# counter_defender_mk_2.net
KiCad netlist of a schematic drawn in EAGLE
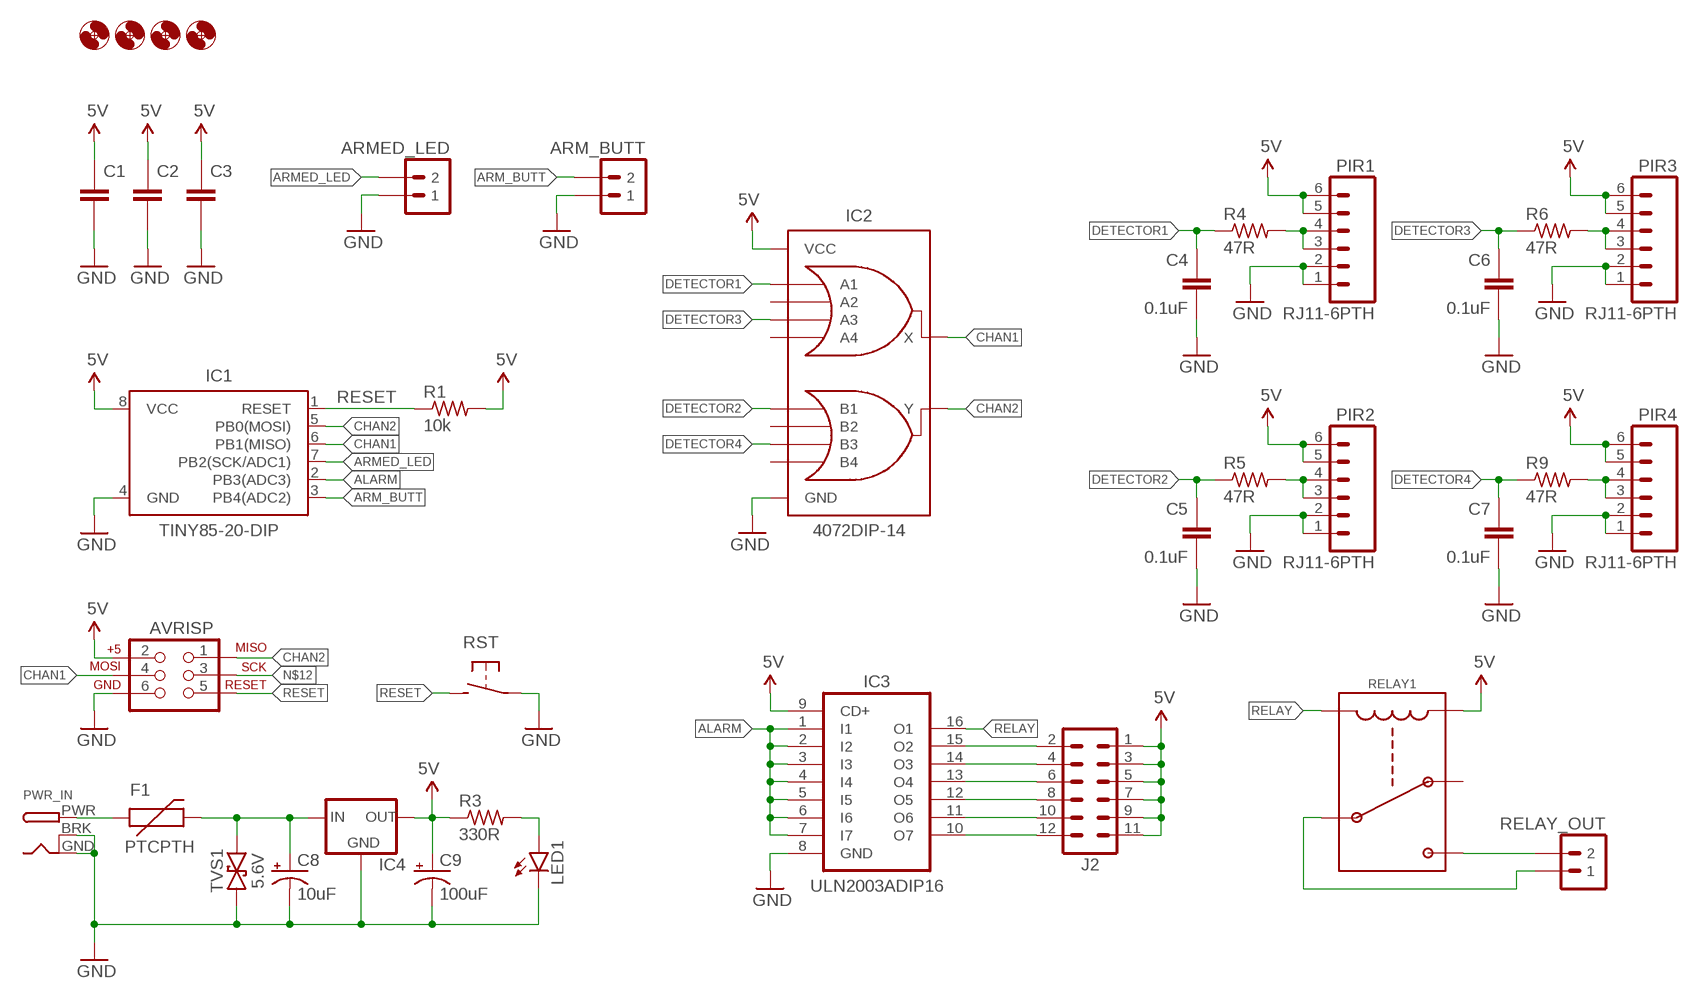
[diagram p0: schematic, sheet 1]

(export (version "E")
  (design (tool "Eeschema 10.0.6"))
  (components
    (comp (ref "ARMED_LED")
      (value "M02JST-PTH-VERT")
      (footprint "eagle-import:JST-2-PH-VERT-PTH")
      (libsource (lib "eagle-import") (part "M02JST-PTH-VERT"))
    )
    (comp (ref "ARM_BUTT")
      (value "M02JST-PTH-VERT")
      (footprint "eagle-import:JST-2-PH-VERT-PTH")
      (libsource (lib "eagle-import") (part "M02JST-PTH-VERT"))
    )
    (comp (ref "AVRISP")
      (value "AVR_SPI_PRG_6PTH")
      (footprint "eagle-import:2X3")
      (libsource (lib "eagle-import") (part "AVR_SPI_PRG_6PTH"))
    )
    (comp (ref "C1")
      (value "CAPACITOR-CERAMIC025-024X044")
      (footprint "eagle-import:C025-024X044")
      (libsource (lib "eagle-import") (part "CAPACITOR-CERAMIC025-024X044"))
    )
    (comp (ref "C2")
      (value "CAPACITOR-CERAMIC025-024X044")
      (footprint "eagle-import:C025-024X044")
      (libsource (lib "eagle-import") (part "CAPACITOR-CERAMIC025-024X044"))
    )
    (comp (ref "C3")
      (value "CAPACITOR-CERAMIC025-024X044")
      (footprint "eagle-import:C025-024X044")
      (libsource (lib "eagle-import") (part "CAPACITOR-CERAMIC025-024X044"))
    )
    (comp (ref "C4")
      (value "0.1uF")
      (footprint "eagle-import:C025-024X044")
      (libsource (lib "eagle-import") (part "CAPACITOR-CERAMIC025-024X044"))
    )
    (comp (ref "C5")
      (value "0.1uF")
      (footprint "eagle-import:C025-024X044")
      (libsource (lib "eagle-import") (part "CAPACITOR-CERAMIC025-024X044"))
    )
    (comp (ref "C6")
      (value "0.1uF")
      (footprint "eagle-import:C025-024X044")
      (libsource (lib "eagle-import") (part "CAPACITOR-CERAMIC025-024X044"))
    )
    (comp (ref "C7")
      (value "0.1uF")
      (footprint "eagle-import:C025-024X044")
      (libsource (lib "eagle-import") (part "CAPACITOR-CERAMIC025-024X044"))
    )
    (comp (ref "C8")
      (value "10uF")
      (footprint "eagle-import:E2-5")
      (libsource (lib "eagle-import") (part "CAPACITOR-POLARIZEDE2-5"))
    )
    (comp (ref "C9")
      (value "100uF")
      (footprint "eagle-import:E2,5-6")
      (libsource (lib "eagle-import") (part "CAPACITOR-POLARIZEDE2.5-6"))
    )
    (comp (ref "F1")
      (value "PTCPTH")
      (footprint "eagle-import:PTC")
      (libsource (lib "eagle-import") (part "PTCPTH"))
    )
    (comp (ref "H1")
      (value "HOLE#2")
      (footprint "eagle-import:HOLE-#2")
      (libsource (lib "eagle-import") (part "HOLE#2"))
    )
    (comp (ref "H2")
      (value "HOLE#2")
      (footprint "eagle-import:HOLE-#2")
      (libsource (lib "eagle-import") (part "HOLE#2"))
    )
    (comp (ref "H3")
      (value "HOLE#2")
      (footprint "eagle-import:HOLE-#2")
      (libsource (lib "eagle-import") (part "HOLE#2"))
    )
    (comp (ref "H4")
      (value "HOLE#2")
      (footprint "eagle-import:HOLE-#2")
      (libsource (lib "eagle-import") (part "HOLE#2"))
    )
    (comp (ref "IC1")
      (value "TINY85-20-DIP")
      (footprint "eagle-import:DIP08")
      (libsource (lib "eagle-import") (part "ATTINY45TINY85-20-DIP"))
    )
    (comp (ref "IC2")
      (value "4072DIP-14")
      (footprint "eagle-import:DIL14")
      (libsource (lib "eagle-import") (part "4072DIP-14"))
    )
    (comp (ref "IC3")
      (value "ULN2003ADIP16")
      (footprint "eagle-import:DIL16")
      (libsource (lib "eagle-import") (part "ULN2003ADIP16"))
    )
    (comp (ref "IC4")
      (value "L7805")
      (footprint "eagle-import:TO220V")
      (libsource (lib "eagle-import") (part "V_REG_78XXTO-220-IGO-VERT"))
    )
    (comp (ref "J2")
      (value "M06X2PTH")
      (footprint "eagle-import:2X6_PTH")
      (libsource (lib "eagle-import") (part "M06X2PTH"))
    )
    (comp (ref "LED1")
      (value "LED3MM")
      (footprint "eagle-import:LED3MM")
      (libsource (lib "eagle-import") (part "LED3MM"))
    )
    (comp (ref "PIR1")
      (value "RJ11-6PTH")
      (footprint "eagle-import:RJ11-6")
      (libsource (lib "eagle-import") (part "RJ11-6PTH"))
    )
    (comp (ref "PIR2")
      (value "RJ11-6PTH")
      (footprint "eagle-import:RJ11-6")
      (libsource (lib "eagle-import") (part "RJ11-6PTH"))
    )
    (comp (ref "PIR3")
      (value "RJ11-6PTH")
      (footprint "eagle-import:RJ11-6")
      (libsource (lib "eagle-import") (part "RJ11-6PTH"))
    )
    (comp (ref "PIR4")
      (value "RJ11-6PTH")
      (footprint "eagle-import:RJ11-6")
      (libsource (lib "eagle-import") (part "RJ11-6PTH"))
    )
    (comp (ref "PWR_IN")
      (value "DCBARRELPTH")
      (footprint "eagle-import:DCJACK_2MM_PTH")
      (libsource (lib "eagle-import") (part "DCBARRELPTH"))
    )
    (comp (ref "R1")
      (value "10k")
      (footprint "eagle-import:RESISTOR-AXIAL-PTH-6.35MM")
      (libsource (lib "eagle-import") (part "RESISTORPTH-AXIAL-6.35MM"))
    )
    (comp (ref "R3")
      (value "330R")
      (footprint "eagle-import:RESISTOR-AXIAL-PTH-6.35MM")
      (libsource (lib "eagle-import") (part "RESISTORPTH-AXIAL-6.35MM"))
    )
    (comp (ref "R4")
      (value "47R")
      (footprint "eagle-import:RESISTOR-AXIAL-PTH-6.35MM")
      (libsource (lib "eagle-import") (part "RESISTORPTH-AXIAL-6.35MM"))
    )
    (comp (ref "R5")
      (value "47R")
      (footprint "eagle-import:RESISTOR-AXIAL-PTH-6.35MM")
      (libsource (lib "eagle-import") (part "RESISTORPTH-AXIAL-6.35MM"))
    )
    (comp (ref "R6")
      (value "47R")
      (footprint "eagle-import:RESISTOR-AXIAL-PTH-6.35MM")
      (libsource (lib "eagle-import") (part "RESISTORPTH-AXIAL-6.35MM"))
    )
    (comp (ref "R9")
      (value "47R")
      (footprint "eagle-import:RESISTOR-AXIAL-PTH-6.35MM")
      (libsource (lib "eagle-import") (part "RESISTORPTH-AXIAL-6.35MM"))
    )
    (comp (ref "RELAY1")
      (value "RELAY-SPDTMC25120")
      (footprint "eagle-import:RELAY-SPDT-MC25120")
      (libsource (lib "eagle-import") (part "RELAY-SPDTMC25120"))
    )
    (comp (ref "RELAY_OUT")
      (value "M02SCREWTERM_2.54MM")
      (footprint "eagle-import:1X02_2.54_SCREWTERM")
      (libsource (lib "eagle-import") (part "M02SCREWTERM_2.54MM"))
    )
    (comp (ref "RST")
      (value "SPST-NO-TACT6MM-PTH")
      (footprint "eagle-import:DTS-6")
      (libsource (lib "eagle-import") (part "SPST-NO-TACT6MM-PTH"))
    )
    (comp (ref "TVS1")
      (value "5.6V")
      (footprint "eagle-import:DO-41-TVS")
      (libsource (lib "eagle-import") (part "TVSDO-41-TVS-BIDIRECTIONAL"))
    )
  )
  (nets
    (net (code "1") (name "5V") (class "Default")
      (node (ref "AVRISP") (pin "2") (pinfunction "2_2") (pintype "passive"))
      (node (ref "C1") (pin "1") (pinfunction "1_1") (pintype "passive"))
      (node (ref "C2") (pin "1") (pinfunction "1_1") (pintype "passive"))
      (node (ref "C3") (pin "1") (pinfunction "1_1") (pintype "passive"))
      (node (ref "C9") (pin "+") (pinfunction "+_+") (pintype "passive"))
      (node (ref "IC1") (pin "8") (pinfunction "VCC_8") (pintype "bidirectional"))
      (node (ref "IC2") (pin "14") (pinfunction "VCC_14") (pintype "bidirectional"))
      (node (ref "IC3") (pin "9") (pinfunction "CD+_9") (pintype "passive"))
      (node (ref "IC4") (pin "3") (pinfunction "OUT_3") (pintype "output"))
      (node (ref "J2") (pin "1") (pinfunction "1_1") (pintype "passive"))
      (node (ref "J2") (pin "11") (pinfunction "11_11") (pintype "passive"))
      (node (ref "J2") (pin "3") (pinfunction "3_3") (pintype "passive"))
      (node (ref "J2") (pin "5") (pinfunction "5_5") (pintype "passive"))
      (node (ref "J2") (pin "7") (pinfunction "7_7") (pintype "passive"))
      (node (ref "J2") (pin "9") (pinfunction "9_9") (pintype "passive"))
      (node (ref "PIR1") (pin "5") (pinfunction "5_5") (pintype "passive"))
      (node (ref "PIR1") (pin "6") (pinfunction "6_6") (pintype "passive"))
      (node (ref "PIR2") (pin "5") (pinfunction "5_5") (pintype "passive"))
      (node (ref "PIR2") (pin "6") (pinfunction "6_6") (pintype "passive"))
      (node (ref "PIR3") (pin "5") (pinfunction "5_5") (pintype "passive"))
      (node (ref "PIR3") (pin "6") (pinfunction "6_6") (pintype "passive"))
      (node (ref "PIR4") (pin "5") (pinfunction "5_5") (pintype "passive"))
      (node (ref "PIR4") (pin "6") (pinfunction "6_6") (pintype "passive"))
      (node (ref "R1") (pin "P$2") (pinfunction "2_P$2") (pintype "passive"))
      (node (ref "R3") (pin "P$1") (pinfunction "1_P$1") (pintype "passive"))
      (node (ref "RELAY1") (pin "CNTL2") (pinfunction "C$1_CNTL2") (pintype "bidirectional"))
    )
    (net (code "2") (name "ALARM") (class "Default")
      (node (ref "IC1") (pin "2") (pinfunction "PB3(ADC3)_2") (pintype "bidirectional"))
      (node (ref "IC3") (pin "1") (pinfunction "I1_1") (pintype "input"))
      (node (ref "IC3") (pin "2") (pinfunction "I2_2") (pintype "input"))
      (node (ref "IC3") (pin "3") (pinfunction "I3_3") (pintype "input"))
      (node (ref "IC3") (pin "4") (pinfunction "I4_4") (pintype "input"))
      (node (ref "IC3") (pin "5") (pinfunction "I5_5") (pintype "input"))
      (node (ref "IC3") (pin "6") (pinfunction "I6_6") (pintype "input"))
      (node (ref "IC3") (pin "7") (pinfunction "I7_7") (pintype "input"))
    )
    (net (code "3") (name "ARMED_LED") (class "Default")
      (node (ref "ARMED_LED") (pin "2") (pinfunction "2_2") (pintype "passive"))
      (node (ref "IC1") (pin "7") (pinfunction "PB2(SCK/ADC1)_7") (pintype "bidirectional"))
    )
    (net (code "4") (name "ARM_BUTT") (class "Default")
      (node (ref "ARM_BUTT") (pin "2") (pinfunction "2_2") (pintype "passive"))
      (node (ref "IC1") (pin "3") (pinfunction "PB4(ADC2)_3") (pintype "bidirectional"))
    )
    (net (code "5") (name "CHAN1") (class "Default")
      (node (ref "AVRISP") (pin "4") (pinfunction "4_4") (pintype "passive"))
      (node (ref "IC1") (pin "6") (pinfunction "PB1(MISO)_6") (pintype "bidirectional"))
      (node (ref "IC2") (pin "1") (pinfunction "X_1") (pintype "bidirectional"))
    )
    (net (code "6") (name "CHAN2") (class "Default")
      (node (ref "AVRISP") (pin "1") (pinfunction "1_1") (pintype "passive"))
      (node (ref "IC1") (pin "5") (pinfunction "PB0(MOSI)_5") (pintype "bidirectional"))
      (node (ref "IC2") (pin "13") (pinfunction "Y_13") (pintype "bidirectional"))
    )
    (net (code "7") (name "DETECTOR1") (class "Default")
      (node (ref "C4") (pin "1") (pinfunction "1_1") (pintype "passive"))
      (node (ref "IC2") (pin "2") (pinfunction "A1_2") (pintype "bidirectional"))
      (node (ref "R4") (pin "P$1") (pinfunction "1_P$1") (pintype "passive"))
    )
    (net (code "8") (name "DETECTOR2") (class "Default")
      (node (ref "C5") (pin "1") (pinfunction "1_1") (pintype "passive"))
      (node (ref "IC2") (pin "9") (pinfunction "B1_9") (pintype "bidirectional"))
      (node (ref "R5") (pin "P$1") (pinfunction "1_P$1") (pintype "passive"))
    )
    (net (code "9") (name "DETECTOR3") (class "Default")
      (node (ref "C6") (pin "1") (pinfunction "1_1") (pintype "passive"))
      (node (ref "IC2") (pin "4") (pinfunction "A3_4") (pintype "bidirectional"))
      (node (ref "R6") (pin "P$1") (pinfunction "1_P$1") (pintype "passive"))
    )
    (net (code "10") (name "DETECTOR4") (class "Default")
      (node (ref "C7") (pin "1") (pinfunction "1_1") (pintype "passive"))
      (node (ref "IC2") (pin "11") (pinfunction "B3_11") (pintype "bidirectional"))
      (node (ref "R9") (pin "P$1") (pinfunction "1_P$1") (pintype "passive"))
    )
    (net (code "11") (name "GND") (class "Default")
      (node (ref "ARMED_LED") (pin "1") (pinfunction "1_1") (pintype "passive"))
      (node (ref "ARM_BUTT") (pin "1") (pinfunction "1_1") (pintype "passive"))
      (node (ref "AVRISP") (pin "6") (pinfunction "6_6") (pintype "passive"))
      (node (ref "C1") (pin "2") (pinfunction "2_2") (pintype "passive"))
      (node (ref "C2") (pin "2") (pinfunction "2_2") (pintype "passive"))
      (node (ref "C3") (pin "2") (pinfunction "2_2") (pintype "passive"))
      (node (ref "C4") (pin "2") (pinfunction "2_2") (pintype "passive"))
      (node (ref "C5") (pin "2") (pinfunction "2_2") (pintype "passive"))
      (node (ref "C6") (pin "2") (pinfunction "2_2") (pintype "passive"))
      (node (ref "C7") (pin "2") (pinfunction "2_2") (pintype "passive"))
      (node (ref "C8") (pin "-") (pinfunction "-_-") (pintype "passive"))
      (node (ref "C9") (pin "-") (pinfunction "-_-") (pintype "passive"))
      (node (ref "IC1") (pin "4") (pinfunction "GND_4") (pintype "bidirectional"))
      (node (ref "IC2") (pin "7") (pinfunction "GND_7") (pintype "bidirectional"))
      (node (ref "IC3") (pin "8") (pinfunction "GND_8") (pintype "power_in"))
      (node (ref "IC4") (pin "2") (pinfunction "GND_2") (pintype "input"))
      (node (ref "LED1") (pin "K") (pinfunction "C_K") (pintype "passive"))
      (node (ref "PIR1") (pin "1") (pinfunction "1_1") (pintype "passive"))
      (node (ref "PIR1") (pin "2") (pinfunction "2_2") (pintype "passive"))
      (node (ref "PIR2") (pin "1") (pinfunction "1_1") (pintype "passive"))
      (node (ref "PIR2") (pin "2") (pinfunction "2_2") (pintype "passive"))
      (node (ref "PIR3") (pin "1") (pinfunction "1_1") (pintype "passive"))
      (node (ref "PIR3") (pin "2") (pinfunction "2_2") (pintype "passive"))
      (node (ref "PIR4") (pin "1") (pinfunction "1_1") (pintype "passive"))
      (node (ref "PIR4") (pin "2") (pinfunction "2_2") (pintype "passive"))
      (node (ref "PWR_IN") (pin "BRK") (pinfunction "BRK_BRK") (pintype "power_in"))
      (node (ref "PWR_IN") (pin "GND") (pinfunction "GND_GND") (pintype "power_in"))
      (node (ref "RST") (pin "1") (pinfunction "1_1") (pintype "passive"))
      (node (ref "RST") (pin "2") (pinfunction "1_2") (pintype "passive"))
      (node (ref "TVS1") (pin "P$1") (pinfunction "1_P$1") (pintype "passive"))
    )
    (net (code "12") (name "N$12") (class "Default")
      (node (ref "AVRISP") (pin "3") (pinfunction "3_3") (pintype "passive"))
    )
    (net (code "13") (name "Net-(F1-1)") (class "Default")
      (node (ref "F1") (pin "P$1") (pinfunction "1_P$1") (pintype "bidirectional"))
      (node (ref "PWR_IN") (pin "PWR") (pinfunction "PWR_PWR") (pintype "power_in"))
    )
    (net (code "14") (name "Net-(F1-2)") (class "Default")
      (node (ref "C8") (pin "+") (pinfunction "+_+") (pintype "passive"))
      (node (ref "F1") (pin "P$2") (pinfunction "2_P$2") (pintype "bidirectional"))
      (node (ref "IC4") (pin "1") (pinfunction "IN_1") (pintype "input"))
      (node (ref "TVS1") (pin "P$2") (pinfunction "2_P$2") (pintype "passive"))
    )
    (net (code "15") (name "Net-(IC3-O2)") (class "Default")
      (node (ref "IC3") (pin "15") (pinfunction "O2_15") (pintype "open_collector"))
      (node (ref "J2") (pin "2") (pinfunction "2_2") (pintype "passive"))
    )
    (net (code "16") (name "Net-(IC3-O3)") (class "Default")
      (node (ref "IC3") (pin "14") (pinfunction "O3_14") (pintype "open_collector"))
      (node (ref "J2") (pin "4") (pinfunction "4_4") (pintype "passive"))
    )
    (net (code "17") (name "Net-(IC3-O4)") (class "Default")
      (node (ref "IC3") (pin "13") (pinfunction "O4_13") (pintype "open_collector"))
      (node (ref "J2") (pin "6") (pinfunction "6_6") (pintype "passive"))
    )
    (net (code "18") (name "Net-(IC3-O5)") (class "Default")
      (node (ref "IC3") (pin "12") (pinfunction "O5_12") (pintype "open_collector"))
      (node (ref "J2") (pin "8") (pinfunction "8_8") (pintype "passive"))
    )
    (net (code "19") (name "Net-(IC3-O6)") (class "Default")
      (node (ref "IC3") (pin "11") (pinfunction "O6_11") (pintype "open_collector"))
      (node (ref "J2") (pin "10") (pinfunction "10_10") (pintype "passive"))
    )
    (net (code "20") (name "Net-(IC3-O7)") (class "Default")
      (node (ref "IC3") (pin "10") (pinfunction "O7_10") (pintype "open_collector"))
      (node (ref "J2") (pin "12") (pinfunction "12_12") (pintype "passive"))
    )
    (net (code "21") (name "Net-(R3-2)") (class "Default")
      (node (ref "LED1") (pin "A") (pinfunction "A_A") (pintype "passive"))
      (node (ref "R3") (pin "P$2") (pinfunction "2_P$2") (pintype "passive"))
    )
    (net (code "22") (name "Net-(R4-2)") (class "Default")
      (node (ref "PIR1") (pin "3") (pinfunction "3_3") (pintype "passive"))
      (node (ref "PIR1") (pin "4") (pinfunction "4_4") (pintype "passive"))
      (node (ref "R4") (pin "P$2") (pinfunction "2_P$2") (pintype "passive"))
    )
    (net (code "23") (name "Net-(R5-2)") (class "Default")
      (node (ref "PIR2") (pin "3") (pinfunction "3_3") (pintype "passive"))
      (node (ref "PIR2") (pin "4") (pinfunction "4_4") (pintype "passive"))
      (node (ref "R5") (pin "P$2") (pinfunction "2_P$2") (pintype "passive"))
    )
    (net (code "24") (name "Net-(R6-2)") (class "Default")
      (node (ref "PIR3") (pin "3") (pinfunction "3_3") (pintype "passive"))
      (node (ref "PIR3") (pin "4") (pinfunction "4_4") (pintype "passive"))
      (node (ref "R6") (pin "P$2") (pinfunction "2_P$2") (pintype "passive"))
    )
    (net (code "25") (name "Net-(R9-2)") (class "Default")
      (node (ref "PIR4") (pin "3") (pinfunction "3_3") (pintype "passive"))
      (node (ref "PIR4") (pin "4") (pinfunction "4_4") (pintype "passive"))
      (node (ref "R9") (pin "P$2") (pinfunction "2_P$2") (pintype "passive"))
    )
    (net (code "26") (name "Net-(RELAY_OUT-1)") (class "Default")
      (node (ref "RELAY1") (pin "COM") (pinfunction "COM_COM") (pintype "bidirectional"))
      (node (ref "RELAY1") (pin "COM2") (pinfunction "COM_COM2") (pintype "bidirectional"))
      (node (ref "RELAY_OUT") (pin "P1") (pinfunction "1_P1") (pintype "passive"))
    )
    (net (code "27") (name "Net-(RELAY_OUT-2)") (class "Default")
      (node (ref "RELAY1") (pin "NO") (pinfunction "NO_NO") (pintype "bidirectional"))
      (node (ref "RELAY_OUT") (pin "P2") (pinfunction "2_P2") (pintype "passive"))
    )
    (net (code "28") (name "RELAY") (class "Default")
      (node (ref "IC3") (pin "16") (pinfunction "O1_16") (pintype "open_collector"))
      (node (ref "RELAY1") (pin "CNTL1") (pinfunction "C$2_CNTL1") (pintype "bidirectional"))
    )
    (net (code "29") (name "RESET") (class "Default")
      (node (ref "AVRISP") (pin "5") (pinfunction "5_5") (pintype "passive"))
      (node (ref "IC1") (pin "1") (pinfunction "RESET_1") (pintype "bidirectional"))
      (node (ref "R1") (pin "P$1") (pinfunction "1_P$1") (pintype "passive"))
      (node (ref "RST") (pin "3") (pinfunction "2_3") (pintype "passive"))
      (node (ref "RST") (pin "4") (pinfunction "2_4") (pintype "passive"))
    )
    (net (code "30") (name "unconnected-(IC2-A2-Pad3)") (class "Default")
      (node (ref "IC2") (pin "3") (pinfunction "A2_3") (pintype "bidirectional"))
    )
    (net (code "31") (name "unconnected-(IC2-A4-Pad5)") (class "Default")
      (node (ref "IC2") (pin "5") (pinfunction "A4_5") (pintype "bidirectional"))
    )
    (net (code "32") (name "unconnected-(IC2-B2-Pad10)") (class "Default")
      (node (ref "IC2") (pin "10") (pinfunction "B2_10") (pintype "bidirectional"))
    )
    (net (code "33") (name "unconnected-(IC2-B4-Pad12)") (class "Default")
      (node (ref "IC2") (pin "12") (pinfunction "B4_12") (pintype "bidirectional"))
    )
    (net (code "34") (name "unconnected-(RELAY1-PadNC)") (class "Default")
      (node (ref "RELAY1") (pin "NC") (pinfunction "NC_NC") (pintype "bidirectional"))
    )
  )
)
